# shield.net
KiCad netlist of a schematic drawn in EAGLE
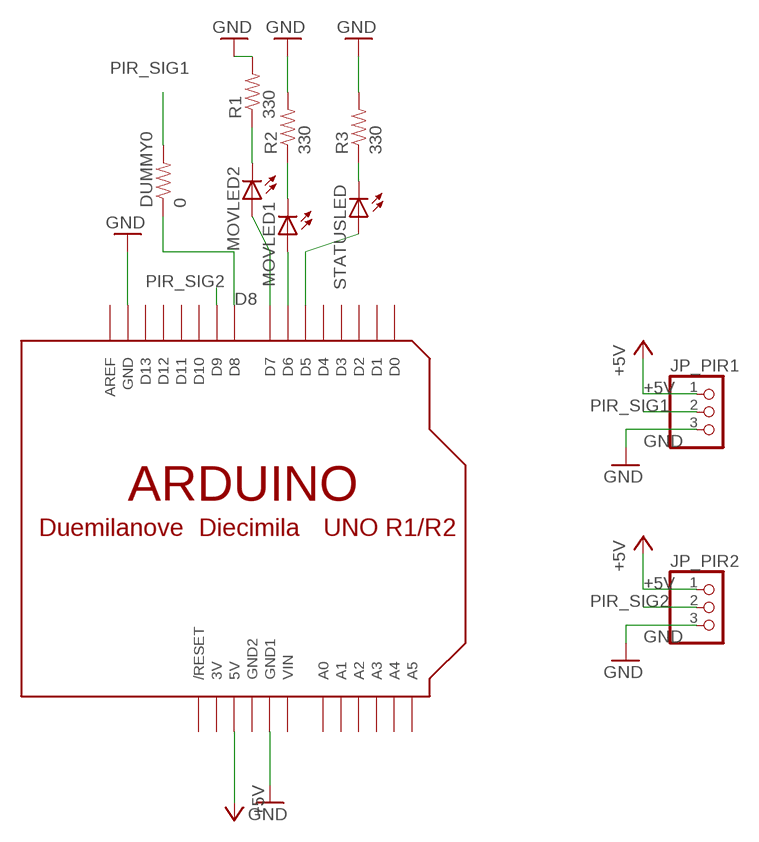
[diagram p0: schematic, sheet 1]

(export (version "E")
  (design (tool "Eeschema 10.0.6"))
  (components
    (comp (ref "DUMMY0")
      (value "0")
      (footprint "eagle-import:AXIAL-0.4")
      (libsource (lib "eagle-import") (part "RESISTORPTH-1/4W"))
    )
    (comp (ref "JP_PIR1")
      (value "PINHD-1X3")
      (footprint "eagle-import:1X03")
      (libsource (lib "eagle-import") (part "PINHD-1X3"))
    )
    (comp (ref "JP_PIR2")
      (value "PINHD-1X3")
      (footprint "eagle-import:1X03")
      (libsource (lib "eagle-import") (part "PINHD-1X3"))
    )
    (comp (ref "MOVLED1")
      (value "LED5MM")
      (footprint "eagle-import:LED5MM")
      (libsource (lib "eagle-import") (part "LED5MM"))
    )
    (comp (ref "MOVLED2")
      (value "LED5MM")
      (footprint "eagle-import:LED5MM")
      (libsource (lib "eagle-import") (part "LED5MM"))
    )
    (comp (ref "R1")
      (value "330")
      (footprint "eagle-import:AXIAL-0.4")
      (libsource (lib "eagle-import") (part "RESISTORPTH-1/4W"))
    )
    (comp (ref "R2")
      (value "330")
      (footprint "eagle-import:AXIAL-0.4")
      (libsource (lib "eagle-import") (part "RESISTORPTH-1/4W"))
    )
    (comp (ref "R3")
      (value "330")
      (footprint "eagle-import:AXIAL-0.4")
      (libsource (lib "eagle-import") (part "RESISTORPTH-1/4W"))
    )
    (comp (ref "STATUSLED")
      (value "LED5MM")
      (footprint "eagle-import:LED5MM")
      (libsource (lib "eagle-import") (part "LED5MM"))
    )
    (comp (ref "U$1")
      (value "ARDUINOUNO")
      (footprint "eagle-import:ARDUINO")
      (libsource (lib "eagle-import") (part "ARDUINOUNO"))
    )
  )
  (nets
    (net (code "1") (name "+5V") (class "Default")
      (node (ref "JP_PIR1") (pin "1") (pinfunction "1_1") (pintype "passive"))
      (node (ref "JP_PIR2") (pin "1") (pinfunction "1_1") (pintype "passive"))
      (node (ref "U$1") (pin "5V") (pinfunction "5V_5V") (pintype "power_in"))
    )
    (net (code "2") (name "/3V") (class "Default")
      (node (ref "U$1") (pin "3V") (pinfunction "3V_3V") (pintype "power_in"))
    )
    (net (code "3") (name "/D8") (class "Default")
      (node (ref "DUMMY0") (pin "P$1") (pinfunction "1_P$1") (pintype "passive"))
      (node (ref "U$1") (pin "D8") (pinfunction "D8_D8") (pintype "bidirectional"))
    )
    (net (code "4") (name "/GND2") (class "Default")
      (node (ref "U$1") (pin "GND2") (pinfunction "GND2_GND2") (pintype "power_in"))
    )
    (net (code "5") (name "/PIR_SIG1") (class "Default")
      (node (ref "DUMMY0") (pin "P$2") (pinfunction "2_P$2") (pintype "passive"))
      (node (ref "JP_PIR1") (pin "2") (pinfunction "2_2") (pintype "passive"))
    )
    (net (code "6") (name "/PIR_SIG2") (class "Default")
      (node (ref "JP_PIR2") (pin "2") (pinfunction "2_2") (pintype "passive"))
      (node (ref "U$1") (pin "D9") (pinfunction "D9_D9") (pintype "bidirectional"))
    )
    (net (code "7") (name "/VIN") (class "Default")
      (node (ref "U$1") (pin "VIN") (pinfunction "VIN_VIN") (pintype "power_in"))
    )
    (net (code "8") (name "GND") (class "Default")
      (node (ref "JP_PIR1") (pin "3") (pinfunction "3_3") (pintype "passive"))
      (node (ref "JP_PIR2") (pin "3") (pinfunction "3_3") (pintype "passive"))
      (node (ref "R1") (pin "P$2") (pinfunction "2_P$2") (pintype "passive"))
      (node (ref "R2") (pin "P$2") (pinfunction "2_P$2") (pintype "passive"))
      (node (ref "R3") (pin "P$2") (pinfunction "2_P$2") (pintype "passive"))
      (node (ref "U$1") (pin "GND") (pinfunction "GND_GND") (pintype "power_in"))
      (node (ref "U$1") (pin "GND1") (pinfunction "GND1_GND1") (pintype "power_in"))
    )
    (net (code "9") (name "Net-(MOVLED1-C)") (class "Default")
      (node (ref "MOVLED1") (pin "K") (pinfunction "C_K") (pintype "passive"))
      (node (ref "R2") (pin "P$1") (pinfunction "1_P$1") (pintype "passive"))
    )
    (net (code "10") (name "Net-(MOVLED1-PadA)") (class "Default")
      (node (ref "MOVLED1") (pin "A") (pinfunction "A_A") (pintype "passive"))
      (node (ref "U$1") (pin "D6") (pinfunction "D6_D6") (pintype "bidirectional"))
    )
    (net (code "11") (name "Net-(MOVLED2-C)") (class "Default")
      (node (ref "MOVLED2") (pin "K") (pinfunction "C_K") (pintype "passive"))
      (node (ref "R1") (pin "P$1") (pinfunction "1_P$1") (pintype "passive"))
    )
    (net (code "12") (name "Net-(MOVLED2-PadA)") (class "Default")
      (node (ref "MOVLED2") (pin "A") (pinfunction "A_A") (pintype "passive"))
      (node (ref "U$1") (pin "D7") (pinfunction "D7_D7") (pintype "bidirectional"))
    )
    (net (code "13") (name "Net-(R3-1)") (class "Default")
      (node (ref "R3") (pin "P$1") (pinfunction "1_P$1") (pintype "passive"))
      (node (ref "STATUSLED") (pin "K") (pinfunction "C_K") (pintype "passive"))
    )
    (net (code "14") (name "Net-(STATUSLED-PadA)") (class "Default")
      (node (ref "STATUSLED") (pin "A") (pinfunction "A_A") (pintype "passive"))
      (node (ref "U$1") (pin "D5") (pinfunction "D5_D5") (pintype "bidirectional"))
    )
    (net (code "15") (name "unconnected-(U$1-PadA0)") (class "Default")
      (node (ref "U$1") (pin "A0") (pinfunction "A0_A0") (pintype "bidirectional"))
    )
    (net (code "16") (name "unconnected-(U$1-PadA1)") (class "Default")
      (node (ref "U$1") (pin "A1") (pinfunction "A1_A1") (pintype "bidirectional"))
    )
    (net (code "17") (name "unconnected-(U$1-PadA2)") (class "Default")
      (node (ref "U$1") (pin "A2") (pinfunction "A2_A2") (pintype "bidirectional"))
    )
    (net (code "18") (name "unconnected-(U$1-PadA3)") (class "Default")
      (node (ref "U$1") (pin "A3") (pinfunction "A3_A3") (pintype "bidirectional"))
    )
    (net (code "19") (name "unconnected-(U$1-PadA4)") (class "Default")
      (node (ref "U$1") (pin "A4") (pinfunction "A4_A4") (pintype "bidirectional"))
    )
    (net (code "20") (name "unconnected-(U$1-PadA5)") (class "Default")
      (node (ref "U$1") (pin "A5") (pinfunction "A5_A5") (pintype "bidirectional"))
    )
    (net (code "21") (name "unconnected-(U$1-PadAREF)") (class "Default")
      (node (ref "U$1") (pin "AREF") (pinfunction "AREF_AREF") (pintype "bidirectional"))
    )
    (net (code "22") (name "unconnected-(U$1-PadD0)") (class "Default")
      (node (ref "U$1") (pin "D0") (pinfunction "D0_D0") (pintype "bidirectional"))
    )
    (net (code "23") (name "unconnected-(U$1-PadD1)") (class "Default")
      (node (ref "U$1") (pin "D1") (pinfunction "D1_D1") (pintype "bidirectional"))
    )
    (net (code "24") (name "unconnected-(U$1-PadD2)") (class "Default")
      (node (ref "U$1") (pin "D2") (pinfunction "D2_D2") (pintype "bidirectional"))
    )
    (net (code "25") (name "unconnected-(U$1-PadD3)") (class "Default")
      (node (ref "U$1") (pin "D3") (pinfunction "D3_D3") (pintype "bidirectional"))
    )
    (net (code "26") (name "unconnected-(U$1-PadD4)") (class "Default")
      (node (ref "U$1") (pin "D4") (pinfunction "D4_D4") (pintype "bidirectional"))
    )
    (net (code "27") (name "unconnected-(U$1-PadD10)") (class "Default")
      (node (ref "U$1") (pin "D10") (pinfunction "D10_D10") (pintype "bidirectional"))
    )
    (net (code "28") (name "unconnected-(U$1-PadD11)") (class "Default")
      (node (ref "U$1") (pin "D11") (pinfunction "D11_D11") (pintype "bidirectional"))
    )
    (net (code "29") (name "unconnected-(U$1-PadD12)") (class "Default")
      (node (ref "U$1") (pin "D12") (pinfunction "D12_D12") (pintype "bidirectional"))
    )
    (net (code "30") (name "unconnected-(U$1-PadD13)") (class "Default")
      (node (ref "U$1") (pin "D13") (pinfunction "D13_D13") (pintype "bidirectional"))
    )
    (net (code "31") (name "unconnected-(U$1-{slash}RESET-PadRESET)") (class "Default")
      (node (ref "U$1") (pin "RESET") (pinfunction "/RESET_RESET") (pintype "bidirectional"))
    )
  )
)
